# TU_PWR.net
KiCad netlist of a schematic drawn in Altium Designer
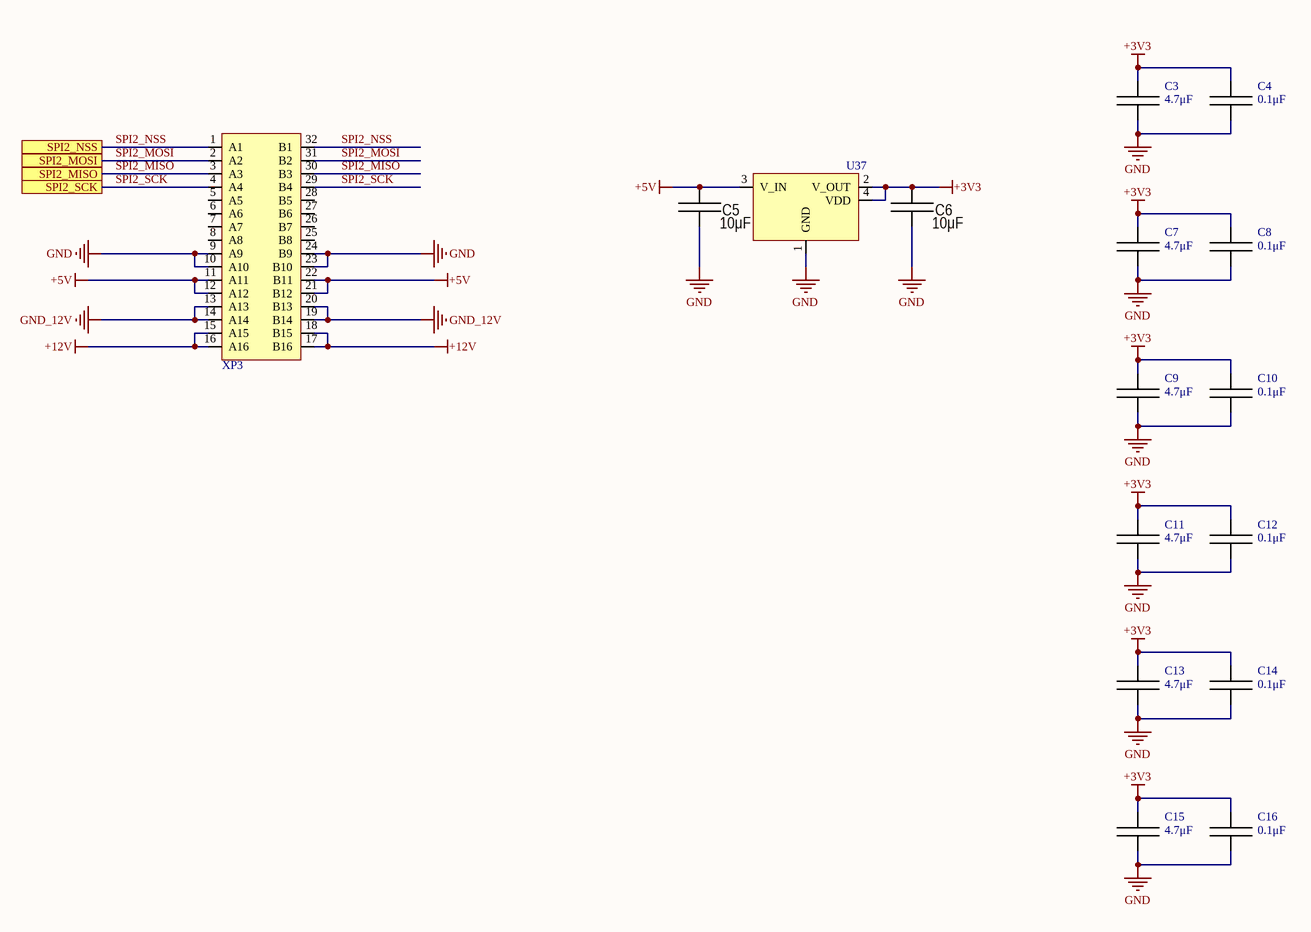
[diagram p0: TU_PWR.SchDoc]

(export (version "E")
  (design (tool "Eeschema 10.0.6"))
  (components
    (comp (ref "C3")
      (value "4.7μF")
      (footprint "CAP: 0603")
      (fields (field (name "VOLTAGE") "25V") (field (name "Comment") "Cap_0603"))
      (libsource (lib "capacitor") (part "Cap_0603"))
    )
    (comp (ref "C4")
      (value "0.1μF")
      (footprint "CAP: 0603")
      (fields (field (name "VOLTAGE") "16V") (field (name "Comment") "Cap_0603"))
      (libsource (lib "capacitor") (part "Cap_0603"))
    )
    (comp (ref "C5")
      (value "10μF")
      (footprint "CAP: 1210")
      (fields
        (field (name "MANUFACTURER") "Yageo")
        (field (name "PARTNUMBER") "CC1210KKX7R9BB104")
        (field (name "VALUEMANUFACTURERPARTNUMBER") "Ceramic capacitor, 10μF, X7R, ±10%, , 1210, -55...+125°C")
      )
      (libsource (lib "capacitor") (part "Ceramic_1210"))
    )
    (comp (ref "C6")
      (value "10μF")
      (footprint "CAP: 1210")
      (fields
        (field (name "MANUFACTURER") "Yageo")
        (field (name "PARTNUMBER") "CC1210KKX7R9BB104")
        (field (name "VALUEMANUFACTURERPARTNUMBER") "Ceramic capacitor, 10μF, X7R, ±10%, , 1210, -55...+125°C")
      )
      (libsource (lib "capacitor") (part "Ceramic_1210"))
    )
    (comp (ref "C7")
      (value "4.7μF")
      (footprint "CAP: 0603")
      (fields (field (name "VOLTAGE") "25V") (field (name "Comment") "Cap_0603"))
      (libsource (lib "capacitor") (part "Cap_0603"))
    )
    (comp (ref "C8")
      (value "0.1μF")
      (footprint "CAP: 0603")
      (fields (field (name "VOLTAGE") "16V") (field (name "Comment") "Cap_0603"))
      (libsource (lib "capacitor") (part "Cap_0603"))
    )
    (comp (ref "C9")
      (value "4.7μF")
      (footprint "CAP: 0603")
      (fields (field (name "VOLTAGE") "25V") (field (name "Comment") "Cap_0603"))
      (libsource (lib "capacitor") (part "Cap_0603"))
    )
    (comp (ref "C10")
      (value "0.1μF")
      (footprint "CAP: 0603")
      (fields (field (name "VOLTAGE") "16V") (field (name "Comment") "Cap_0603"))
      (libsource (lib "capacitor") (part "Cap_0603"))
    )
    (comp (ref "C11")
      (value "4.7μF")
      (footprint "CAP: 0603")
      (fields (field (name "VOLTAGE") "25V") (field (name "Comment") "Cap_0603"))
      (libsource (lib "capacitor") (part "Cap_0603"))
    )
    (comp (ref "C12")
      (value "0.1μF")
      (footprint "CAP: 0603")
      (fields (field (name "VOLTAGE") "16V") (field (name "Comment") "Cap_0603"))
      (libsource (lib "capacitor") (part "Cap_0603"))
    )
    (comp (ref "C13")
      (value "4.7μF")
      (footprint "CAP: 0603")
      (fields (field (name "VOLTAGE") "25V") (field (name "Comment") "Cap_0603"))
      (libsource (lib "capacitor") (part "Cap_0603"))
    )
    (comp (ref "C14")
      (value "0.1μF")
      (footprint "CAP: 0603")
      (fields (field (name "VOLTAGE") "16V") (field (name "Comment") "Cap_0603"))
      (libsource (lib "capacitor") (part "Cap_0603"))
    )
    (comp (ref "C15")
      (value "4.7μF")
      (footprint "CAP: 0603")
      (fields (field (name "VOLTAGE") "25V") (field (name "Comment") "Cap_0603"))
      (libsource (lib "capacitor") (part "Cap_0603"))
    )
    (comp (ref "C16")
      (value "0.1μF")
      (footprint "CAP: 0603")
      (fields (field (name "VOLTAGE") "16V") (field (name "Comment") "Cap_0603"))
      (libsource (lib "capacitor") (part "Cap_0603"))
    )
    (comp (ref "U37")
      (value "LD1117S33CTR4")
      (footprint "SOT-223-3")
      (description "LDO Voltage Regulator 3.3V 0.8A Positive")
      (fields (field (name "MANUFACTURER") "STMicroelectronics"))
      (libsource (lib "MY_INT_LIB") (part "LD1117S33CTR"))
    )
    (comp (ref "XP3")
      (value "DS1118-32M-R23")
      (footprint "DS1118-32M-R23")
      (description "DIN 41612 Connector")
      (fields (field (name "MANUFACTURER") "Connfly"))
      (libsource (lib "MY_INT_LIB") (part "DS1118-32M-R23"))
    )
  )
  (nets
    (net (code "1") (name "+3V3") (class "Default")
      (node (ref "C10") (pin "2") (pinfunction "2_2") (pintype "passive"))
      (node (ref "C11") (pin "2") (pinfunction "2_2") (pintype "passive"))
      (node (ref "C12") (pin "2") (pinfunction "2_2") (pintype "passive"))
      (node (ref "C13") (pin "2") (pinfunction "2_2") (pintype "passive"))
      (node (ref "C14") (pin "2") (pinfunction "2_2") (pintype "passive"))
      (node (ref "C15") (pin "2") (pinfunction "2_2") (pintype "passive"))
      (node (ref "C16") (pin "2") (pinfunction "2_2") (pintype "passive"))
      (node (ref "C3") (pin "2") (pinfunction "2_2") (pintype "passive"))
      (node (ref "C4") (pin "2") (pinfunction "2_2") (pintype "passive"))
      (node (ref "C6") (pin "2") (pinfunction "2_2") (pintype "passive"))
      (node (ref "C7") (pin "2") (pinfunction "2_2") (pintype "passive"))
      (node (ref "C8") (pin "2") (pinfunction "2_2") (pintype "passive"))
      (node (ref "C9") (pin "2") (pinfunction "2_2") (pintype "passive"))
      (node (ref "U37") (pin "2") (pinfunction "V_OUT_2") (pintype "power_in"))
      (node (ref "U37") (pin "4") (pinfunction "VDD_4") (pintype "power_in"))
    )
    (net (code "2") (name "+5V") (class "Default")
      (node (ref "C5") (pin "2") (pinfunction "2_2") (pintype "passive"))
      (node (ref "U37") (pin "3") (pinfunction "V_IN_3") (pintype "power_in"))
      (node (ref "XP3") (pin "11") (pinfunction "A11_11") (pintype "passive"))
      (node (ref "XP3") (pin "12") (pinfunction "A12_12") (pintype "passive"))
      (node (ref "XP3") (pin "21") (pinfunction "B12_21") (pintype "passive"))
      (node (ref "XP3") (pin "22") (pinfunction "B11_22") (pintype "passive"))
    )
    (net (code "3") (name "+12V") (class "Default")
      (node (ref "XP3") (pin "15") (pinfunction "A15_15") (pintype "passive"))
      (node (ref "XP3") (pin "16") (pinfunction "A16_16") (pintype "passive"))
      (node (ref "XP3") (pin "17") (pinfunction "B16_17") (pintype "passive"))
      (node (ref "XP3") (pin "18") (pinfunction "B15_18") (pintype "passive"))
    )
    (net (code "4") (name "/SPI2_MISO") (class "Default")
      (node (ref "XP3") (pin "3") (pinfunction "A3_3") (pintype "passive"))
      (node (ref "XP3") (pin "30") (pinfunction "B3_30") (pintype "passive"))
    )
    (net (code "5") (name "/SPI2_MOSI") (class "Default")
      (node (ref "XP3") (pin "2") (pinfunction "A2_2") (pintype "passive"))
      (node (ref "XP3") (pin "31") (pinfunction "B2_31") (pintype "passive"))
    )
    (net (code "6") (name "/SPI2_NSS") (class "Default")
      (node (ref "XP3") (pin "1") (pinfunction "A1_1") (pintype "passive"))
      (node (ref "XP3") (pin "32") (pinfunction "B1_32") (pintype "passive"))
    )
    (net (code "7") (name "/SPI2_SCK") (class "Default")
      (node (ref "XP3") (pin "29") (pinfunction "B4_29") (pintype "passive"))
      (node (ref "XP3") (pin "4") (pinfunction "A4_4") (pintype "passive"))
    )
    (net (code "8") (name "GND") (class "Default")
      (node (ref "C10") (pin "1") (pinfunction "1_1") (pintype "passive"))
      (node (ref "C11") (pin "1") (pinfunction "1_1") (pintype "passive"))
      (node (ref "C12") (pin "1") (pinfunction "1_1") (pintype "passive"))
      (node (ref "C13") (pin "1") (pinfunction "1_1") (pintype "passive"))
      (node (ref "C14") (pin "1") (pinfunction "1_1") (pintype "passive"))
      (node (ref "C15") (pin "1") (pinfunction "1_1") (pintype "passive"))
      (node (ref "C16") (pin "1") (pinfunction "1_1") (pintype "passive"))
      (node (ref "C3") (pin "1") (pinfunction "1_1") (pintype "passive"))
      (node (ref "C4") (pin "1") (pinfunction "1_1") (pintype "passive"))
      (node (ref "C5") (pin "1") (pinfunction "1_1") (pintype "passive"))
      (node (ref "C6") (pin "1") (pinfunction "1_1") (pintype "passive"))
      (node (ref "C7") (pin "1") (pinfunction "1_1") (pintype "passive"))
      (node (ref "C8") (pin "1") (pinfunction "1_1") (pintype "passive"))
      (node (ref "C9") (pin "1") (pinfunction "1_1") (pintype "passive"))
      (node (ref "U37") (pin "1") (pinfunction "GND_1") (pintype "power_in"))
      (node (ref "XP3") (pin "10") (pinfunction "A10_10") (pintype "passive"))
      (node (ref "XP3") (pin "23") (pinfunction "B10_23") (pintype "passive"))
      (node (ref "XP3") (pin "24") (pinfunction "B9_24") (pintype "passive"))
      (node (ref "XP3") (pin "9") (pinfunction "A9_9") (pintype "passive"))
    )
    (net (code "9") (name "GND_12V") (class "Default")
      (node (ref "XP3") (pin "13") (pinfunction "A13_13") (pintype "passive"))
      (node (ref "XP3") (pin "14") (pinfunction "A14_14") (pintype "passive"))
      (node (ref "XP3") (pin "19") (pinfunction "B14_19") (pintype "passive"))
      (node (ref "XP3") (pin "20") (pinfunction "B13_20") (pintype "passive"))
    )
    (net (code "10") (name "unconnected-(XP3-A5-Pad5)") (class "Default")
      (node (ref "XP3") (pin "5") (pinfunction "A5_5") (pintype "passive"))
    )
    (net (code "11") (name "unconnected-(XP3-A6-Pad6)") (class "Default")
      (node (ref "XP3") (pin "6") (pinfunction "A6_6") (pintype "passive"))
    )
    (net (code "12") (name "unconnected-(XP3-A7-Pad7)") (class "Default")
      (node (ref "XP3") (pin "7") (pinfunction "A7_7") (pintype "passive"))
    )
    (net (code "13") (name "unconnected-(XP3-A8-Pad8)") (class "Default")
      (node (ref "XP3") (pin "8") (pinfunction "A8_8") (pintype "passive"))
    )
    (net (code "14") (name "unconnected-(XP3-B5-Pad28)") (class "Default")
      (node (ref "XP3") (pin "28") (pinfunction "B5_28") (pintype "passive"))
    )
    (net (code "15") (name "unconnected-(XP3-B6-Pad27)") (class "Default")
      (node (ref "XP3") (pin "27") (pinfunction "B6_27") (pintype "passive"))
    )
    (net (code "16") (name "unconnected-(XP3-B7-Pad26)") (class "Default")
      (node (ref "XP3") (pin "26") (pinfunction "B7_26") (pintype "passive"))
    )
    (net (code "17") (name "unconnected-(XP3-B8-Pad25)") (class "Default")
      (node (ref "XP3") (pin "25") (pinfunction "B8_25") (pintype "passive"))
    )
  )
)
